# MVM_BMS.net
KiCad netlist of a schematic drawn in Altium Designer
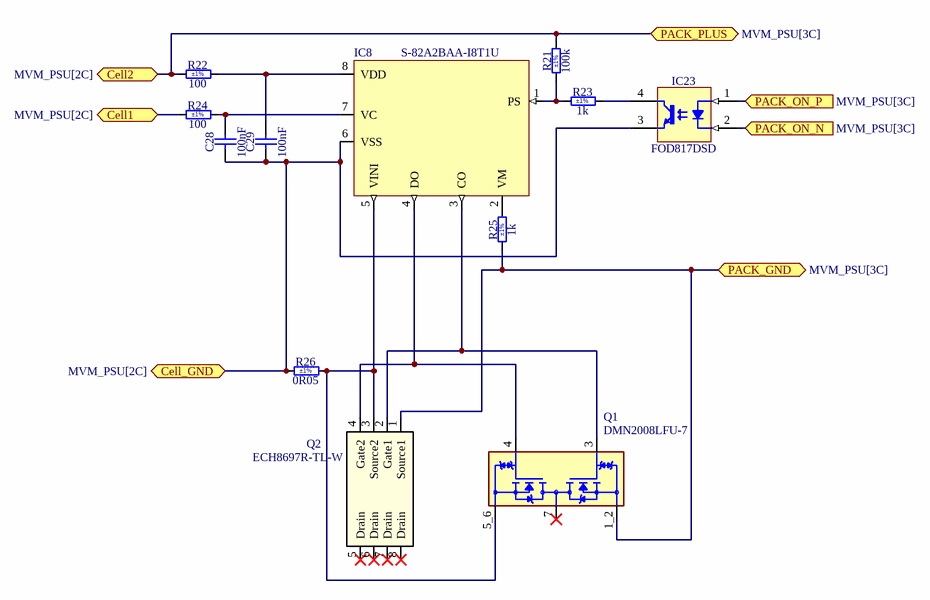
[diagram p0: MVM_BMS.SchDoc]

(export (version "E")
  (design (tool "Eeschema 10.0.6"))
  (components
    (comp (ref "C28")
      (value "100nF")
      (footprint "CAPC2012X88N")
      (description "Non-polarised capacitor")
      (fields
        (field (name "PART NUMBER") "CC0805_100NF_50V_1%_NP0")
        (field (name "VOLTAGE") "50V")
        (field (name "AUTHOR") "CERN DEM HF")
      )
      (libsource (lib "Capacitors") (part "Capacitor - non polarized"))
    )
    (comp (ref "C29")
      (value "100nF")
      (footprint "CAPC2012X88N")
      (description "Non-polarised capacitor")
      (fields
        (field (name "PART NUMBER") "CC0805_100NF_50V_1%_NP0")
        (field (name "VOLTAGE") "50V")
        (field (name "AUTHOR") "CERN DEM HF")
      )
      (libsource (lib "Capacitors") (part "Capacitor - non polarized"))
    )
    (comp (ref "IC8")
      (value "S-82A2BAA-I8T1U")
      (footprint "SON50P200X48-8N")
      (description "BATTERY PROTECTION IC\r\nFOR 2-SERIAL-CELL PACK")
      (fields (field (name "MANUFACTURER") "ABLIC"))
      (libsource (lib "Regulators_SMPS") (part "PM_S-82A2BAA-I8T1U"))
    )
    (comp (ref "IC23")
      (value "FOD817DSD")
      (footprint "FAIRCHILD_FOD817DSD")
      (description "Single Optocoupler")
      (fields (field (name "MANUFACTURER") "FAIRCHILD SEMICONDUCTOR") (field (name "AUTHOR") "CERN DEM JLC"))
      (libsource (lib "ICs And Semiconductors") (part "Optocoupler Type7"))
    )
    (comp (ref "Q1")
      (value "DMN2008LFU-7")
      (footprint "TRANS_DMN2008LFU-7")
      (description "Mosfet Array 2 N-Channel (Dual) Common Drain 20V 14.5A 1W Surface Mount U-DFN2030-6 (Type B)")
      (fields (field (name "DIGI-KEY_PART_NUMBER") "DMN2008LFU-7DICT-ND") (field (name "MF") "Diodes Inc."))
      (libsource (lib "Tranistors_Thyristors") (part "Q_DMN2008LFU-7"))
    )
    (comp (ref "Q2")
      (value "ECH8697R-TL-W")
      (footprint "SOT-28FL-8_2P9X2P3_ONS-M")
      (description "No Description Available")
      (fields (field (name "COPYRIGHT") "Copyright (C) 2018 Accelerated Designs. All rights reserved"))
      (libsource (lib "Tranistors_Thyristors") (part "Q_ECH8697R-TL-W"))
    )
    (comp (ref "R21")
      (value "100k")
      (footprint "RESC1608X55N")
      (description "Resistor - 1%")
      (fields
        (field (name "TOLERANCE") "±1%")
        (field (name "PART NUMBER") "R0603_100K_1%_0.1W_100PPM")
        (field (name "POWER") "0.1W")
        (field (name "AUTHOR") "CERN DEM JLC")
      )
      (libsource (lib "Resistors") (part "Resistor - 1%"))
    )
    (comp (ref "R22")
      (value "100")
      (footprint "RESC1608X55N")
      (description "Resistor - 1%")
      (fields
        (field (name "TOLERANCE") "±1%")
        (field (name "PART NUMBER") "R0603_100R_1%_0.1W_100PPM")
        (field (name "POWER") "0.1W")
        (field (name "AUTHOR") "CERN DEM JLC")
      )
      (libsource (lib "Resistors") (part "Resistor - 1%"))
    )
    (comp (ref "R23")
      (value "1k")
      (footprint "RESC1608X55N")
      (description "Resistor - 1%")
      (fields
        (field (name "TOLERANCE") "±1%")
        (field (name "PART NUMBER") "R0603_1K_1%_0.1W_100PPM")
        (field (name "POWER") "0.1W")
        (field (name "AUTHOR") "CERN DEM JLC")
      )
      (libsource (lib "Resistors") (part "Resistor - 1%"))
    )
    (comp (ref "R24")
      (value "100")
      (footprint "RESC1608X55N")
      (description "Resistor - 1%")
      (fields
        (field (name "TOLERANCE") "±1%")
        (field (name "PART NUMBER") "R0603_100R_1%_0.1W_100PPM")
        (field (name "POWER") "0.1W")
        (field (name "AUTHOR") "CERN DEM JLC")
      )
      (libsource (lib "Resistors") (part "Resistor - 1%"))
    )
    (comp (ref "R25")
      (value "1k")
      (footprint "RESC1608X55N")
      (description "Resistor - 1%")
      (fields
        (field (name "TOLERANCE") "±1%")
        (field (name "PART NUMBER") "R0603_1K_1%_0.1W_100PPM")
        (field (name "POWER") "0.1W")
        (field (name "AUTHOR") "CERN DEM JLC")
      )
      (libsource (lib "Resistors") (part "Resistor - 1%"))
    )
    (comp (ref "R26")
      (value "0R05")
      (footprint "RESC2012X60N")
      (description "Resistor - 1%")
      (fields
        (field (name "TOLERANCE") "±1%")
        (field (name "PART NUMBER") "R0805_0R05_1%_0.25W_300PPM")
        (field (name "POWER") "0.25W")
        (field (name "AUTHOR") "CERN DEM MR")
      )
      (libsource (lib "Resistors") (part "Resistor - 1%"))
    )
  )
  (nets
    (net (code "1") (name "/Cell1") (class "Default")
      (node (ref "R24") (pin "1") (pinfunction "1_1") (pintype "passive"))
    )
    (net (code "2") (name "/Cell2") (class "Default")
      (node (ref "R21") (pin "2") (pinfunction "2_2") (pintype "passive"))
      (node (ref "R22") (pin "1") (pinfunction "1_1") (pintype "passive"))
    )
    (net (code "3") (name "/Cell_GND") (class "Default")
      (node (ref "C28") (pin "1") (pinfunction "1_1") (pintype "passive"))
      (node (ref "C29") (pin "1") (pinfunction "1_1") (pintype "passive"))
      (node (ref "IC23") (pin "3") (pinfunction "E_3") (pintype "open_emitter"))
      (node (ref "IC8") (pin "6") (pinfunction "VSS_6") (pintype "power_in"))
      (node (ref "R26") (pin "1") (pinfunction "1_1") (pintype "passive"))
    )
    (net (code "4") (name "/PACK_GND") (class "Default")
      (node (ref "Q1") (pin "1_2") (pinfunction "S1_1_2") (pintype "passive"))
      (node (ref "Q2") (pin "1") (pinfunction "Source1_1") (pintype "bidirectional"))
      (node (ref "R25") (pin "1") (pinfunction "1_1") (pintype "passive"))
    )
    (net (code "5") (name "/PACK_ON_N") (class "Default")
      (node (ref "IC23") (pin "2") (pinfunction "C_2") (pintype "input"))
    )
    (net (code "6") (name "/PACK_ON_P") (class "Default")
      (node (ref "IC23") (pin "1") (pinfunction "A_1") (pintype "input"))
    )
    (net (code "7") (name "Net-(IC8-CO)") (class "Default")
      (node (ref "IC8") (pin "3") (pinfunction "CO_3") (pintype "output"))
      (node (ref "Q1") (pin "3") (pinfunction "G1_3") (pintype "passive"))
      (node (ref "Q2") (pin "2") (pinfunction "Gate1_2") (pintype "bidirectional"))
    )
    (net (code "8") (name "Net-(IC8-DO)") (class "Default")
      (node (ref "IC8") (pin "4") (pinfunction "DO_4") (pintype "output"))
      (node (ref "Q1") (pin "4") (pinfunction "G2_4") (pintype "passive"))
      (node (ref "Q2") (pin "4") (pinfunction "Gate2_4") (pintype "bidirectional"))
    )
    (net (code "9") (name "Net-(IC8-PS)") (class "Default")
      (node (ref "IC8") (pin "1") (pinfunction "PS_1") (pintype "input"))
      (node (ref "R21") (pin "1") (pinfunction "1_1") (pintype "passive"))
      (node (ref "R23") (pin "1") (pinfunction "1_1") (pintype "passive"))
    )
    (net (code "10") (name "Net-(IC8-VC)") (class "Default")
      (node (ref "C28") (pin "2") (pinfunction "2_2") (pintype "passive"))
      (node (ref "IC8") (pin "7") (pinfunction "VC_7") (pintype "power_in"))
      (node (ref "R24") (pin "2") (pinfunction "2_2") (pintype "passive"))
    )
    (net (code "11") (name "Net-(IC8-VDD)") (class "Default")
      (node (ref "C29") (pin "2") (pinfunction "2_2") (pintype "passive"))
      (node (ref "IC8") (pin "8") (pinfunction "VDD_8") (pintype "power_in"))
      (node (ref "R22") (pin "2") (pinfunction "2_2") (pintype "passive"))
    )
    (net (code "12") (name "Net-(IC8-VINI)") (class "Default")
      (node (ref "IC8") (pin "5") (pinfunction "VINI_5") (pintype "output"))
      (node (ref "Q1") (pin "5_6") (pinfunction "S2_5_6") (pintype "passive"))
      (node (ref "Q2") (pin "3") (pinfunction "Source2_3") (pintype "passive"))
      (node (ref "R26") (pin "2") (pinfunction "2_2") (pintype "passive"))
    )
    (net (code "13") (name "Net-(IC8-VM)") (class "Default")
      (node (ref "IC8") (pin "2") (pinfunction "VM_2") (pintype "power_in"))
      (node (ref "R25") (pin "2") (pinfunction "2_2") (pintype "passive"))
    )
    (net (code "14") (name "Net-(IC23-C-Pad4)") (class "Default")
      (node (ref "IC23") (pin "4") (pinfunction "C_4") (pintype "open_collector"))
      (node (ref "R23") (pin "2") (pinfunction "2_2") (pintype "passive"))
    )
    (net (code "15") (name "unconnected-(Q1-D-Pad7)") (class "Default")
      (node (ref "Q1") (pin "7") (pinfunction "D_7") (pintype "passive+no_connect"))
    )
    (net (code "16") (name "unconnected-(Q2-Drain-Pad5)") (class "Default")
      (node (ref "Q2") (pin "5") (pinfunction "Drain_5") (pintype "passive+no_connect"))
    )
    (net (code "17") (name "unconnected-(Q2-Drain-Pad6)") (class "Default")
      (node (ref "Q2") (pin "6") (pinfunction "Drain_6") (pintype "passive+no_connect"))
    )
    (net (code "18") (name "unconnected-(Q2-Drain-Pad7)") (class "Default")
      (node (ref "Q2") (pin "7") (pinfunction "Drain_7") (pintype "passive+no_connect"))
    )
    (net (code "19") (name "unconnected-(Q2-Drain-Pad8)") (class "Default")
      (node (ref "Q2") (pin "8") (pinfunction "Drain_8") (pintype "passive+no_connect"))
    )
  )
)
